# SuperCap.net
KiCad netlist of a schematic drawn in Altium Designer
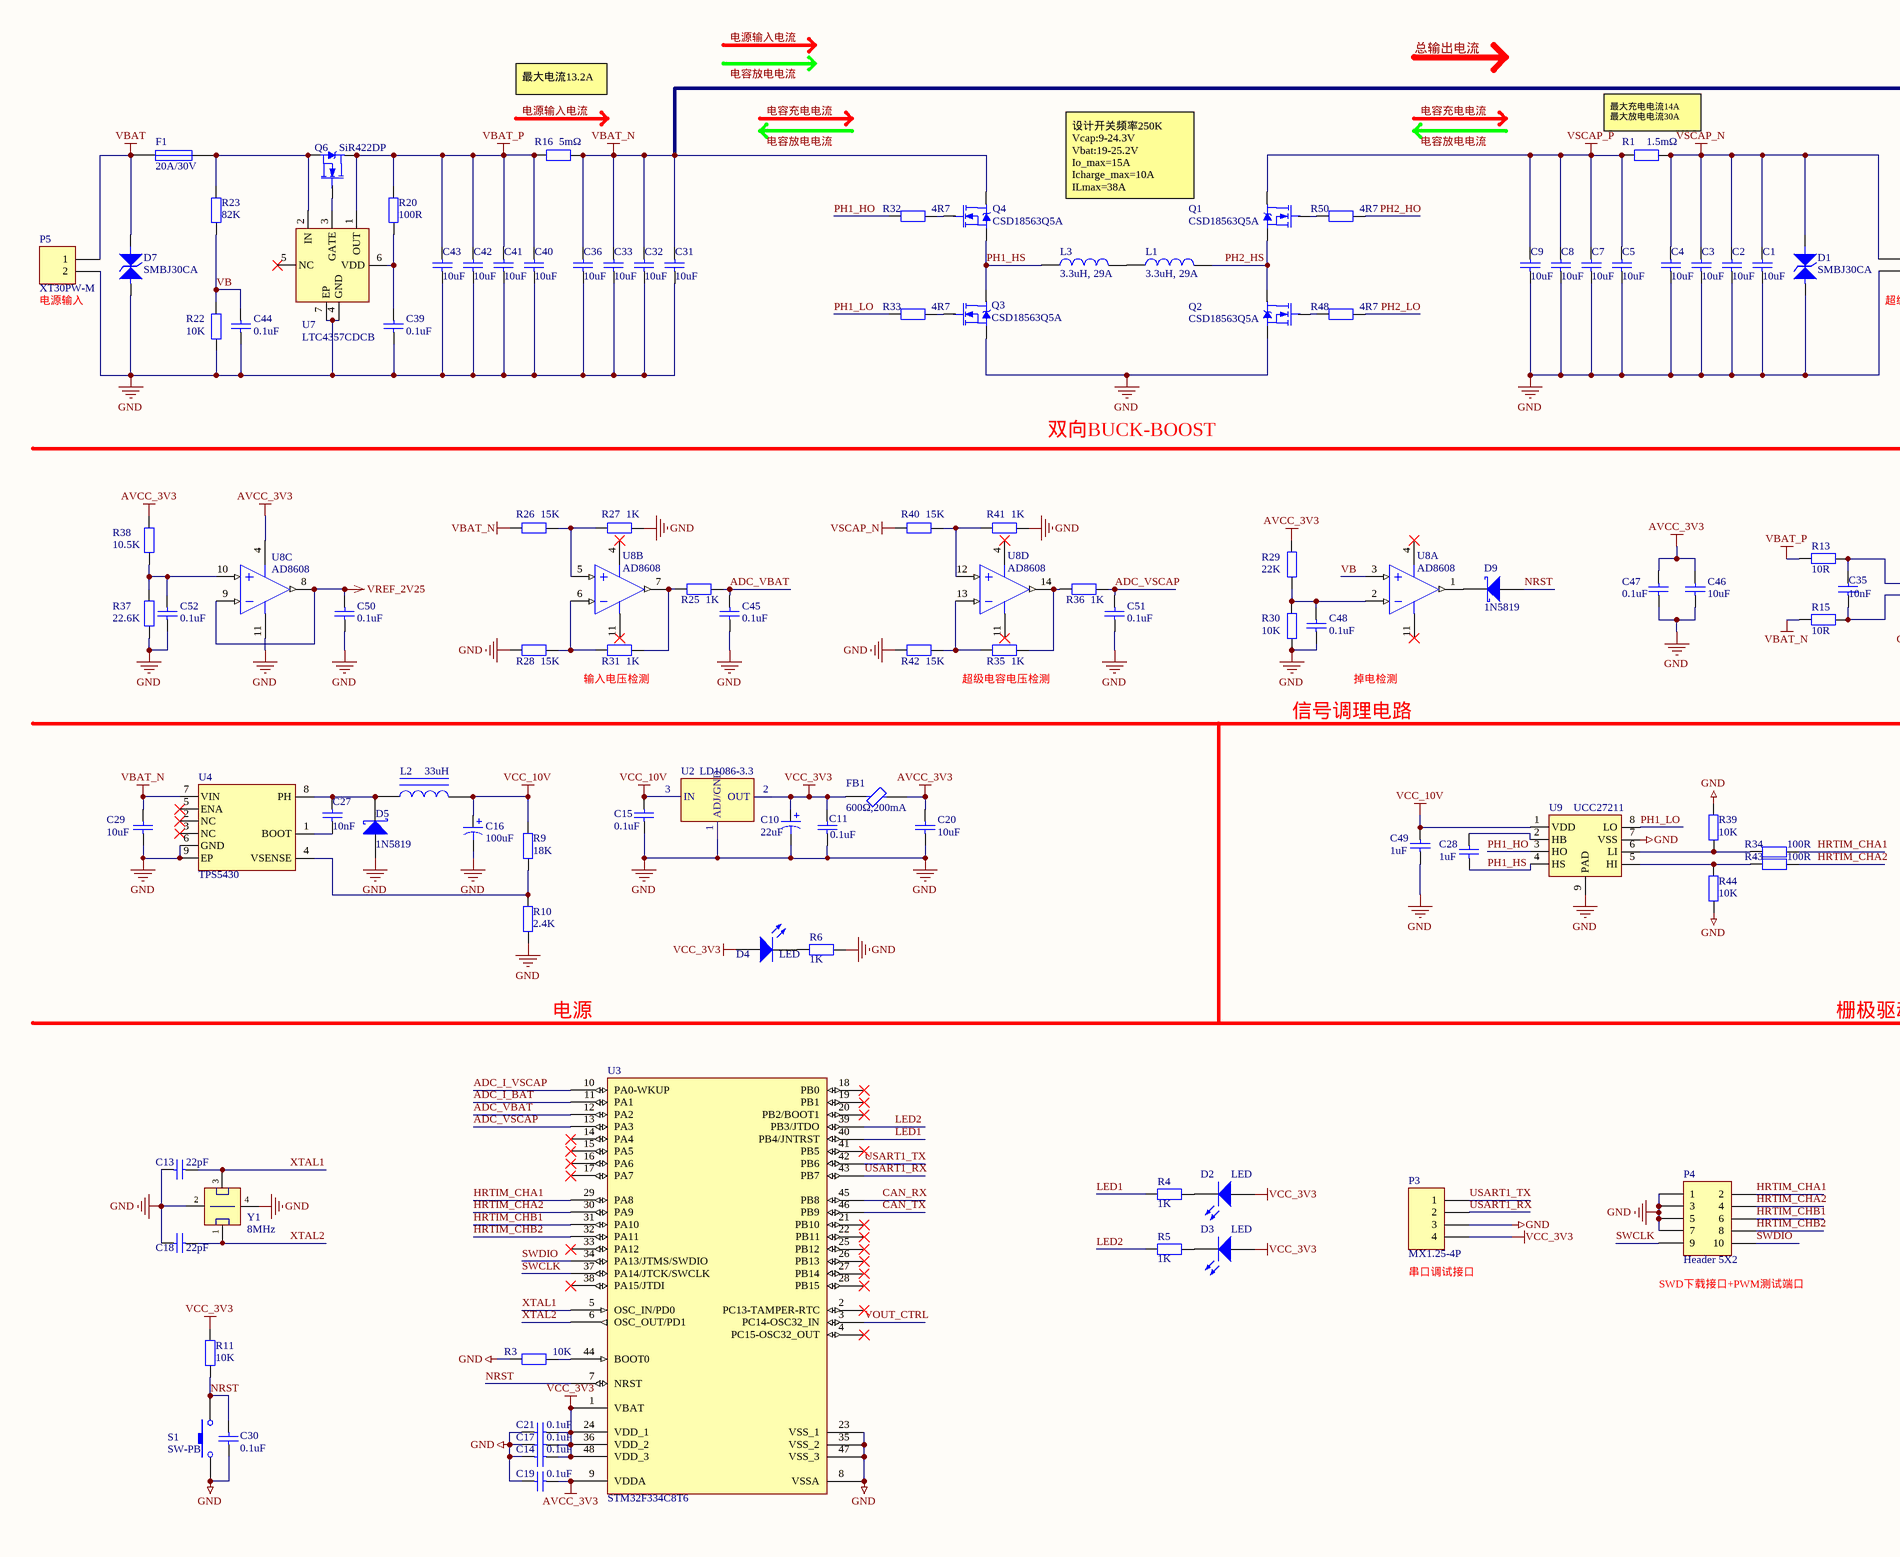
[diagram p0: SuperCap.SchDoc, left]
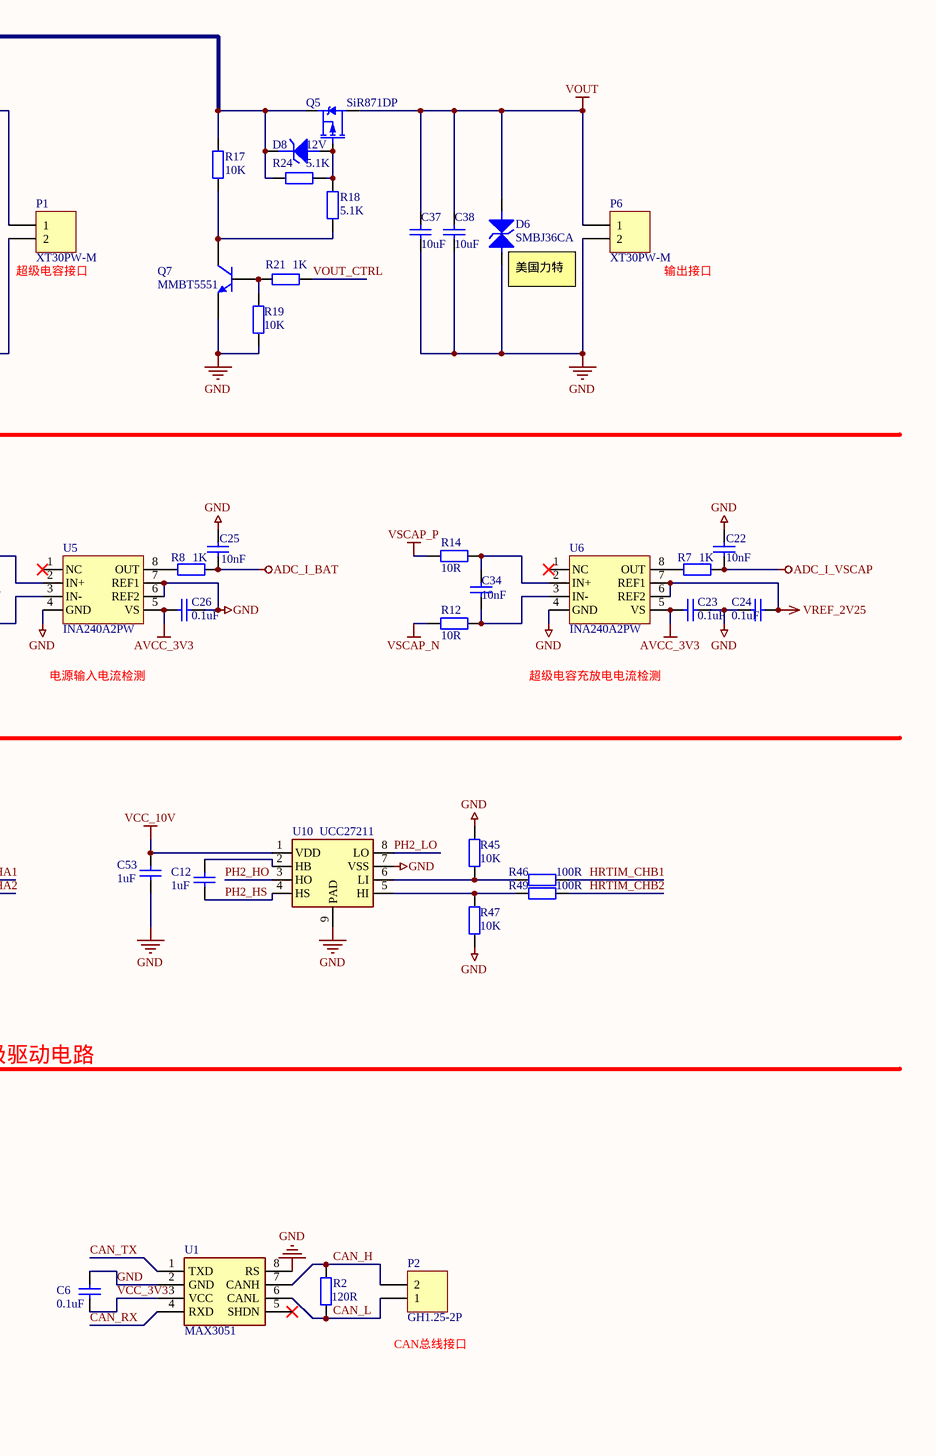
[diagram p1: SuperCap.SchDoc, right]

(export (version "E")
  (design (tool "Eeschema 10.0.6"))
  (components
    (comp (ref "C1")
      (value "10uF")
      (footprint "C 0805_M")
      (description "Capacitor")
      (libsource (lib "Miscellaneous Devices") (part "Cap"))
    )
    (comp (ref "C2")
      (value "10uF")
      (footprint "C 0805_M")
      (description "Capacitor")
      (libsource (lib "Miscellaneous Devices") (part "Cap"))
    )
    (comp (ref "C3")
      (value "10uF")
      (footprint "C 0805_M")
      (description "Capacitor")
      (libsource (lib "Miscellaneous Devices") (part "Cap"))
    )
    (comp (ref "C4")
      (value "10uF")
      (footprint "C 0805_M")
      (description "Capacitor")
      (libsource (lib "Miscellaneous Devices") (part "Cap"))
    )
    (comp (ref "C5")
      (value "10uF")
      (footprint "C 0805_M")
      (description "Capacitor")
      (libsource (lib "Miscellaneous Devices") (part "Cap"))
    )
    (comp (ref "C6")
      (value "0.1uF")
      (footprint "C 0603_M")
      (description "Capacitor")
      (libsource (lib "Miscellaneous Devices") (part "Cap"))
    )
    (comp (ref "C7")
      (value "10uF")
      (footprint "C 0805_M")
      (description "Capacitor")
      (libsource (lib "Miscellaneous Devices") (part "Cap"))
    )
    (comp (ref "C8")
      (value "10uF")
      (footprint "C 0805_M")
      (description "Capacitor")
      (libsource (lib "Miscellaneous Devices") (part "Cap"))
    )
    (comp (ref "C9")
      (value "10uF")
      (footprint "C 0805_M")
      (description "Capacitor")
      (libsource (lib "Miscellaneous Devices") (part "Cap"))
    )
    (comp (ref "C10")
      (value "22uF")
      (footprint "CD B(3528)")
      (description "Polarized Capacitor (Radial)")
      (libsource (lib "Miscellaneous Devices") (part "Cap Pol1"))
    )
    (comp (ref "C11")
      (value "0.1uF")
      (footprint "C 0603_M")
      (description "Capacitor")
      (libsource (lib "Miscellaneous Devices") (part "Cap"))
    )
    (comp (ref "C12")
      (value "1uF")
      (footprint "C 0603_M")
      (description "Capacitor")
      (libsource (lib "Miscellaneous Devices") (part "Cap"))
    )
    (comp (ref "C13")
      (value "22pF")
      (footprint "C 0603_M")
      (description "Capacitor")
      (fields (field (name "PUBLISHER") "Altium Limited"))
      (libsource (lib "Miscellaneous Devices") (part "Cap"))
    )
    (comp (ref "C14")
      (value "0.1uF")
      (footprint "C 0603_M")
      (description "Capacitor")
      (libsource (lib "Miscellaneous Devices") (part "Cap"))
    )
    (comp (ref "C15")
      (value "0.1uF")
      (footprint "C 0603_M")
      (description "Capacitor")
      (libsource (lib "Miscellaneous Devices") (part "Cap"))
    )
    (comp (ref "C16")
      (value "100uF")
      (footprint "CD C(6032)")
      (description "Polarized Capacitor (Radial)")
      (libsource (lib "Miscellaneous Devices") (part "Cap Pol1"))
    )
    (comp (ref "C17")
      (value "0.1uF")
      (footprint "C 0603_M")
      (description "Capacitor")
      (libsource (lib "Miscellaneous Devices") (part "Cap"))
    )
    (comp (ref "C18")
      (value "22pF")
      (footprint "C 0603_M")
      (description "Capacitor")
      (fields (field (name "PUBLISHER") "Altium Limited"))
      (libsource (lib "Miscellaneous Devices") (part "Cap"))
    )
    (comp (ref "C19")
      (value "0.1uF")
      (footprint "C 0603_M")
      (description "Capacitor")
      (libsource (lib "Miscellaneous Devices") (part "Cap"))
    )
    (comp (ref "C20")
      (value "10uF")
      (footprint "C 0603_M")
      (description "Capacitor")
      (libsource (lib "Miscellaneous Devices") (part "Cap"))
    )
    (comp (ref "C21")
      (value "0.1uF")
      (footprint "C 0603_M")
      (description "Capacitor")
      (libsource (lib "Miscellaneous Devices") (part "Cap"))
    )
    (comp (ref "C22")
      (value "10nF")
      (footprint "C 0603_M")
      (description "Capacitor")
      (fields (field (name "PUBLISHER") "Altium Limited"))
      (libsource (lib "Miscellaneous Devices") (part "Cap"))
    )
    (comp (ref "C23")
      (value "0.1uF")
      (footprint "C 0603_M")
      (description "Capacitor")
      (fields (field (name "PUBLISHER") "Altium Limited"))
      (libsource (lib "Miscellaneous Devices") (part "Cap"))
    )
    (comp (ref "C24")
      (value "0.1uF")
      (footprint "C 0603_M")
      (description "Capacitor")
      (fields (field (name "PUBLISHER") "Altium Limited"))
      (libsource (lib "Miscellaneous Devices") (part "Cap"))
    )
    (comp (ref "C25")
      (value "10nF")
      (footprint "C 0603_M")
      (description "Capacitor")
      (fields (field (name "PUBLISHER") "Altium Limited"))
      (libsource (lib "Miscellaneous Devices") (part "Cap"))
    )
    (comp (ref "C26")
      (value "0.1uF")
      (footprint "C 0603_M")
      (description "Capacitor")
      (fields (field (name "PUBLISHER") "Altium Limited"))
      (libsource (lib "Miscellaneous Devices") (part "Cap"))
    )
    (comp (ref "C27")
      (value "10nF")
      (footprint "C 0603_M")
      (description "Capacitor")
      (libsource (lib "Miscellaneous Devices") (part "Cap"))
    )
    (comp (ref "C28")
      (value "1uF")
      (footprint "C 0603_M")
      (description "Capacitor")
      (libsource (lib "Miscellaneous Devices") (part "Cap"))
    )
    (comp (ref "C29")
      (value "10uF")
      (footprint "C 0805_M")
      (description "Capacitor")
      (libsource (lib "Miscellaneous Devices") (part "Cap"))
    )
    (comp (ref "C30")
      (value "0.1uF")
      (footprint "C 0603_M")
      (description "Capacitor")
      (libsource (lib "Miscellaneous Devices") (part "Cap"))
    )
    (comp (ref "C31")
      (value "10uF")
      (footprint "C 0805_M")
      (description "Capacitor")
      (libsource (lib "Miscellaneous Devices") (part "Cap"))
    )
    (comp (ref "C32")
      (value "10uF")
      (footprint "C 0805_M")
      (description "Capacitor")
      (libsource (lib "Miscellaneous Devices") (part "Cap"))
    )
    (comp (ref "C33")
      (value "10uF")
      (footprint "C 0805_M")
      (description "Capacitor")
      (libsource (lib "Miscellaneous Devices") (part "Cap"))
    )
    (comp (ref "C34")
      (value "10nF")
      (footprint "C 0603_M")
      (description "Capacitor")
      (fields (field (name "PUBLISHER") "Altium Limited"))
      (libsource (lib "Miscellaneous Devices") (part "Cap"))
    )
    (comp (ref "C35")
      (value "10nF")
      (footprint "C 0603_M")
      (description "Capacitor")
      (fields (field (name "PUBLISHER") "Altium Limited"))
      (libsource (lib "Miscellaneous Devices") (part "Cap"))
    )
    (comp (ref "C36")
      (value "10uF")
      (footprint "C 0805_M")
      (description "Capacitor")
      (libsource (lib "Miscellaneous Devices") (part "Cap"))
    )
    (comp (ref "C37")
      (value "10uF")
      (footprint "C 0805_M")
      (description "Capacitor")
      (libsource (lib "Miscellaneous Devices") (part "Cap"))
    )
    (comp (ref "C38")
      (value "10uF")
      (footprint "C 0805_M")
      (description "Capacitor")
      (libsource (lib "Miscellaneous Devices") (part "Cap"))
    )
    (comp (ref "C39")
      (value "0.1uF")
      (footprint "C 0603_M")
      (description "Capacitor")
      (libsource (lib "Miscellaneous Devices") (part "Cap"))
    )
    (comp (ref "C40")
      (value "10uF")
      (footprint "C 0805_M")
      (description "Capacitor")
      (libsource (lib "Miscellaneous Devices") (part "Cap"))
    )
    (comp (ref "C41")
      (value "10uF")
      (footprint "C 0805_M")
      (description "Capacitor")
      (libsource (lib "Miscellaneous Devices") (part "Cap"))
    )
    (comp (ref "C42")
      (value "10uF")
      (footprint "C 0805_M")
      (description "Capacitor")
      (libsource (lib "Miscellaneous Devices") (part "Cap"))
    )
    (comp (ref "C43")
      (value "10uF")
      (footprint "C 0805_M")
      (description "Capacitor")
      (libsource (lib "Miscellaneous Devices") (part "Cap"))
    )
    (comp (ref "C44")
      (value "0.1uF")
      (footprint "C 0603_M")
      (description "Capacitor")
      (libsource (lib "Miscellaneous Devices") (part "Cap"))
    )
    (comp (ref "C45")
      (value "0.1uF")
      (footprint "C 0603_M")
      (description "Capacitor")
      (libsource (lib "Miscellaneous Devices") (part "Cap"))
    )
    (comp (ref "C46")
      (value "10uF")
      (footprint "C 0603_M")
      (description "Capacitor")
      (libsource (lib "Miscellaneous Devices") (part "Cap"))
    )
    (comp (ref "C47")
      (value "0.1uF")
      (footprint "C 0603_M")
      (description "Capacitor")
      (libsource (lib "Miscellaneous Devices") (part "Cap"))
    )
    (comp (ref "C48")
      (value "0.1uF")
      (footprint "C 0603_M")
      (description "Capacitor")
      (libsource (lib "Miscellaneous Devices") (part "Cap"))
    )
    (comp (ref "C49")
      (value "1uF")
      (footprint "C 0603_M")
      (description "Capacitor")
      (libsource (lib "Miscellaneous Devices") (part "Cap"))
    )
    (comp (ref "C50")
      (value "0.1uF")
      (footprint "C 0603_M")
      (description "Capacitor")
      (libsource (lib "Miscellaneous Devices") (part "Cap"))
    )
    (comp (ref "C51")
      (value "0.1uF")
      (footprint "C 0603_M")
      (description "Capacitor")
      (libsource (lib "Miscellaneous Devices") (part "Cap"))
    )
    (comp (ref "C52")
      (value "0.1uF")
      (footprint "C 0603_M")
      (description "Capacitor")
      (libsource (lib "Miscellaneous Devices") (part "Cap"))
    )
    (comp (ref "C53")
      (value "1uF")
      (footprint "C 0603_M")
      (description "Capacitor")
      (libsource (lib "Miscellaneous Devices") (part "Cap"))
    )
    (comp (ref "D1")
      (value "SMBJ30CA")
      (footprint "二极管-整流桥:SMB")
      (description "双向瞬态抑制二极管")
      (libsource (lib "二极管") (part "TVS"))
    )
    (comp (ref "D2")
      (value "LED")
      (footprint "LED 0603R")
      (description "Typical INFRARED GaAs LED")
      (libsource (lib "Miscellaneous Devices") (part "LED0"))
    )
    (comp (ref "D3")
      (value "LED")
      (footprint "LED 0603R")
      (description "Typical INFRARED GaAs LED")
      (libsource (lib "Miscellaneous Devices") (part "LED0"))
    )
    (comp (ref "D4")
      (value "LED")
      (footprint "LED 0603R")
      (description "Typical INFRARED GaAs LED")
      (libsource (lib "Miscellaneous Devices") (part "LED0"))
    )
    (comp (ref "D5")
      (value "1N5819")
      (footprint "SMA")
      (description "Schottky Rectifier")
      (libsource (lib "Miscellaneous Devices") (part "Diode 11DQ03"))
    )
    (comp (ref "D6")
      (value "SMBJ36CA")
      (footprint "二极管-整流桥:SMB")
      (description "双向瞬态抑制二极管")
      (libsource (lib "二极管") (part "TVS"))
    )
    (comp (ref "D7")
      (value "SMBJ30CA")
      (footprint "二极管-整流桥:SMB")
      (description "双向瞬态抑制二极管")
      (libsource (lib "二极管") (part "TVS"))
    )
    (comp (ref "D8")
      (value "12V")
      (footprint "SOD-123")
      (description "稳压二极管")
      (libsource (lib "二极管") (part "DIODE ZENER"))
    )
    (comp (ref "D9")
      (value "1N5819")
      (footprint "SOD-323")
      (description "Schottky Diode")
      (fields (field (name "PUBLISHER") "Altium Limited"))
      (libsource (lib "Miscellaneous Devices") (part "D Schottky"))
    )
    (comp (ref "F1")
      (value "20A/30V")
      (footprint "FU 1206")
      (description "Fuse")
      (fields (field (name "PUBLISHER") "Altium Limited"))
      (libsource (lib "Miscellaneous Devices") (part "Fuse 1"))
    )
    (comp (ref "FB1")
      (value "600Ω,200mA")
      (footprint "FB0603_M")
      (libsource (lib "my_library") (part "Ferrite Bead"))
    )
    (comp (ref "L1")
      (value "3.3uH, 29A")
      (footprint "WE-HCI_2212")
      (description "WE-HCI SMT Flat Wire High Current Inductor, size 2212, 3.3uH, 29A")
      (fields
        (field (name "MANUFACTURER PART NUMBER") "74435580330")
        (field (name "MANUFACTURER") "Wurth Elektronik")
      )
      (libsource (lib "WE-HCI (rev20b)") (part "74435580330"))
    )
    (comp (ref "L2")
      (value "33uH")
      (footprint "L-SMD-0630")
      (description "Magnetic-Core Inductor")
      (libsource (lib "Miscellaneous Devices") (part "Inductor Iron"))
    )
    (comp (ref "L3")
      (value "3.3uH, 29A")
      (footprint "WE-HCI_2212")
      (description "WE-HCI SMT Flat Wire High Current Inductor, size 2212, 3.3uH, 29A")
      (fields
        (field (name "MANUFACTURER PART NUMBER") "74435580330")
        (field (name "MANUFACTURER") "Wurth Elektronik")
      )
      (libsource (lib "WE-HCI (rev20b)") (part "74435580330"))
    )
    (comp (ref "P1")
      (value "XT30PW-M")
      (footprint "XT30PW-M")
      (description "Header, 2-Pin")
      (fields (field (name "PUBLISHER") "Altium Limited"))
      (libsource (lib "") (part "Header 2_1"))
    )
    (comp (ref "P2")
      (value "GH1.25-2P")
      (footprint "A1257WR-S-2P")
      (description "Header, 2-Pin")
      (fields (field (name "PUBLISHER") "Altium Limited"))
      (libsource (lib "Miscellaneous Connectors") (part "Header 2"))
    )
    (comp (ref "P3")
      (value "MX1.25-4P")
      (footprint "MX 1.25-WS-4P")
      (description "Header, 4-Pin")
      (fields (field (name "PUBLISHER") "Altium Limited"))
      (libsource (lib "Miscellaneous Connectors") (part "Header 4"))
    )
    (comp (ref "P4")
      (value "Header 5X2")
      (footprint "HDR2.54-LI-2x5P")
      (description "Header, 5-Pin, Dual row")
      (fields (field (name "PUBLISHER") "Altium Limited"))
      (libsource (lib "Miscellaneous Connectors") (part "Header 5X2"))
    )
    (comp (ref "P5")
      (value "XT30PW-M")
      (footprint "XT30PW-M")
      (description "Header, 2-Pin")
      (fields (field (name "PUBLISHER") "Altium Limited"))
      (libsource (lib "") (part "Header 2_2"))
    )
    (comp (ref "P6")
      (value "XT30PW-M")
      (footprint "XT30PW-M")
      (description "Header, 2-Pin")
      (fields (field (name "PUBLISHER") "Altium Limited"))
      (libsource (lib "") (part "Header 2_1"))
    )
    (comp (ref "Q1")
      (value "CSD18563Q5A")
      (footprint "PG-TDSON-8")
      (description "N沟道场效应管")
      (libsource (lib "MOS管") (part "N-MOS"))
    )
    (comp (ref "Q2")
      (value "CSD18563Q5A")
      (footprint "PG-TDSON-8")
      (description "N沟道场效应管")
      (libsource (lib "MOS管") (part "N-MOS"))
    )
    (comp (ref "Q3")
      (value "CSD18563Q5A")
      (footprint "PG-TDSON-8")
      (description "N沟道场效应管")
      (libsource (lib "MOS管") (part "N-MOS"))
    )
    (comp (ref "Q4")
      (value "CSD18563Q5A")
      (footprint "PG-TDSON-8")
      (description "N沟道场效应管")
      (libsource (lib "MOS管") (part "N-MOS"))
    )
    (comp (ref "Q5")
      (value "SiR871DP")
      (footprint "PG-TDSON-8")
      (description "P沟道场效应管")
      (libsource (lib "MOS管") (part "P-MOS"))
    )
    (comp (ref "Q6")
      (value "SiR422DP")
      (footprint "PG-TDSON-8")
      (description "N沟道场效应管")
      (libsource (lib "MOS管") (part "N-MOS"))
    )
    (comp (ref "Q7")
      (value "MMBT5551")
      (footprint "SOT23-3N")
      (description "NPN Bipolar Transistor")
      (fields (field (name "PUBLISHER") "Altium Limited"))
      (libsource (lib "Miscellaneous Devices") (part "NPN"))
    )
    (comp (ref "R1")
      (value "1.5mΩ")
      (footprint "R 2512_M")
      (description "Resistor")
      (fields (field (name "PUBLISHER") "Altium Limited"))
      (libsource (lib "") (part "Res2_1"))
    )
    (comp (ref "R2")
      (value "120R")
      (footprint "R 0603_M")
      (description "Resistor")
      (libsource (lib "") (part "Res2_1"))
    )
    (comp (ref "R3")
      (value "10K")
      (footprint "R 0603_M")
      (description "Resistor")
      (libsource (lib "") (part "Res2_2"))
    )
    (comp (ref "R4")
      (value "1K")
      (footprint "R 0603_M")
      (description "Resistor")
      (libsource (lib "") (part "Res2_2"))
    )
    (comp (ref "R5")
      (value "1K")
      (footprint "R 0603_M")
      (description "Resistor")
      (libsource (lib "") (part "Res2_2"))
    )
    (comp (ref "R6")
      (value "1K")
      (footprint "R 0603_M")
      (description "Resistor")
      (libsource (lib "Miscellaneous Devices") (part "Res2"))
    )
    (comp (ref "R7")
      (value "1K")
      (footprint "R 0603_M")
      (description "Resistor")
      (fields (field (name "PUBLISHER") "Altium Limited"))
      (libsource (lib "") (part "Res2_2"))
    )
    (comp (ref "R8")
      (value "1K")
      (footprint "R 0603_M")
      (description "Resistor")
      (fields (field (name "PUBLISHER") "Altium Limited"))
      (libsource (lib "") (part "Res2_2"))
    )
    (comp (ref "R9")
      (value "18K")
      (footprint "R 0603_M")
      (description "Resistor")
      (libsource (lib "") (part "Res2_1"))
    )
    (comp (ref "R10")
      (value "2.4K")
      (footprint "R 0603_M")
      (description "Resistor")
      (libsource (lib "") (part "Res2_1"))
    )
    (comp (ref "R11")
      (value "10K")
      (footprint "R 0603_M")
      (description "Resistor")
      (libsource (lib "") (part "Res2_3"))
    )
    (comp (ref "R12")
      (value "10R")
      (footprint "R 0603_M")
      (description "Resistor")
      (fields (field (name "PUBLISHER") "Altium Limited"))
      (libsource (lib "") (part "Res2_1"))
    )
    (comp (ref "R13")
      (value "10R")
      (footprint "R 0603_M")
      (description "Resistor")
      (fields (field (name "PUBLISHER") "Altium Limited"))
      (libsource (lib "") (part "Res2_1"))
    )
    (comp (ref "R14")
      (value "10R")
      (footprint "R 0603_M")
      (description "Resistor")
      (fields (field (name "PUBLISHER") "Altium Limited"))
      (libsource (lib "") (part "Res2_1"))
    )
    (comp (ref "R15")
      (value "10R")
      (footprint "R 0603_M")
      (description "Resistor")
      (fields (field (name "PUBLISHER") "Altium Limited"))
      (libsource (lib "") (part "Res2_1"))
    )
    (comp (ref "R16")
      (value "5mΩ")
      (footprint "R 2512_M")
      (description "Resistor")
      (fields (field (name "PUBLISHER") "Altium Limited"))
      (libsource (lib "") (part "Res2_3"))
    )
    (comp (ref "R17")
      (value "10K")
      (footprint "R 0603_M")
      (description "Resistor")
      (libsource (lib "") (part "Res2_3"))
    )
    (comp (ref "R18")
      (value "5.1K")
      (footprint "R 0603_M")
      (description "Resistor")
      (libsource (lib "") (part "Res2_3"))
    )
    (comp (ref "R19")
      (value "10K")
      (footprint "R 0603_M")
      (description "Resistor")
      (libsource (lib "") (part "Res2_1"))
    )
    (comp (ref "R20")
      (value "100R")
      (footprint "R 0603_M")
      (description "Resistor")
      (libsource (lib "") (part "Res2_3"))
    )
    (comp (ref "R21")
      (value "1K")
      (footprint "R 0603_M")
      (description "Resistor")
      (libsource (lib "Miscellaneous Devices") (part "Res2"))
    )
    (comp (ref "R22")
      (value "10K")
      (footprint "R 0603_M")
      (description "Resistor")
      (libsource (lib "") (part "Res2_3"))
    )
    (comp (ref "R23")
      (value "82K")
      (footprint "R 0603_M")
      (description "Resistor")
      (libsource (lib "") (part "Res2_3"))
    )
    (comp (ref "R24")
      (value "5.1K")
      (footprint "R 0603_M")
      (description "Resistor")
      (libsource (lib "Miscellaneous Devices") (part "Res2"))
    )
    (comp (ref "R25")
      (value "1K")
      (footprint "R 0603_M")
      (description "Resistor")
      (libsource (lib "") (part "Res2_2"))
    )
    (comp (ref "R26")
      (value "15K")
      (footprint "R 0603_M")
      (description "Resistor")
      (libsource (lib "") (part "Res2_2"))
    )
    (comp (ref "R27")
      (value "1K")
      (footprint "R 0603_M")
      (description "Resistor")
      (libsource (lib "Miscellaneous Devices") (part "Res2"))
    )
    (comp (ref "R28")
      (value "15K")
      (footprint "R 0603_M")
      (description "Resistor")
      (libsource (lib "") (part "Res2_2"))
    )
    (comp (ref "R29")
      (value "22K")
      (footprint "R 0603_M")
      (description "Resistor")
      (libsource (lib "") (part "Res2_1"))
    )
    (comp (ref "R30")
      (value "10K")
      (footprint "R 0603_M")
      (description "Resistor")
      (libsource (lib "") (part "Res2_1"))
    )
    (comp (ref "R31")
      (value "1K")
      (footprint "R 0603_M")
      (description "Resistor")
      (libsource (lib "") (part "Res2_2"))
    )
    (comp (ref "R32")
      (value "4R7")
      (footprint "R 0805_M")
      (description "Resistor")
      (libsource (lib "") (part "Res2_2"))
    )
    (comp (ref "R33")
      (value "4R7")
      (footprint "R 0805_M")
      (description "Resistor")
      (libsource (lib "") (part "Res2_2"))
    )
    (comp (ref "R34")
      (value "100R")
      (footprint "R 0603_M")
      (description "Resistor")
      (libsource (lib "") (part "Res2_2"))
    )
    (comp (ref "R35")
      (value "1K")
      (footprint "R 0603_M")
      (description "Resistor")
      (libsource (lib "") (part "Res2_2"))
    )
    (comp (ref "R36")
      (value "1K")
      (footprint "R 0603_M")
      (description "Resistor")
      (libsource (lib "") (part "Res2_2"))
    )
    (comp (ref "R37")
      (value "22.6K")
      (footprint "R 0603_M")
      (description "Resistor")
      (libsource (lib "") (part "Res2_1"))
    )
    (comp (ref "R38")
      (value "10.5K")
      (footprint "R 0603_M")
      (description "Resistor")
      (libsource (lib "") (part "Res2_1"))
    )
    (comp (ref "R39")
      (value "10K")
      (footprint "R 0603_M")
      (description "Resistor")
      (libsource (lib "") (part "Res2_1"))
    )
    (comp (ref "R40")
      (value "15K")
      (footprint "R 0603_M")
      (description "Resistor")
      (libsource (lib "") (part "Res2_2"))
    )
    (comp (ref "R41")
      (value "1K")
      (footprint "R 0603_M")
      (description "Resistor")
      (libsource (lib "Miscellaneous Devices") (part "Res2"))
    )
    (comp (ref "R42")
      (value "15K")
      (footprint "R 0603_M")
      (description "Resistor")
      (libsource (lib "") (part "Res2_2"))
    )
    (comp (ref "R43")
      (value "100R")
      (footprint "R 0603_M")
      (description "Resistor")
      (libsource (lib "") (part "Res2_2"))
    )
    (comp (ref "R44")
      (value "10K")
      (footprint "R 0603_M")
      (description "Resistor")
      (libsource (lib "") (part "Res2_1"))
    )
    (comp (ref "R45")
      (value "10K")
      (footprint "R 0603_M")
      (description "Resistor")
      (libsource (lib "") (part "Res2_1"))
    )
    (comp (ref "R46")
      (value "100R")
      (footprint "R 0603_M")
      (description "Resistor")
      (libsource (lib "") (part "Res2_2"))
    )
    (comp (ref "R47")
      (value "10K")
      (footprint "R 0603_M")
      (description "Resistor")
      (libsource (lib "") (part "Res2_1"))
    )
    (comp (ref "R48")
      (value "4R7")
      (footprint "R 0805_M")
      (description "Resistor")
      (libsource (lib "") (part "Res2_2"))
    )
    (comp (ref "R49")
      (value "100R")
      (footprint "R 0603_M")
      (description "Resistor")
      (libsource (lib "") (part "Res2_2"))
    )
    (comp (ref "R50")
      (value "4R7")
      (footprint "R 0805_M")
      (description "Resistor")
      (libsource (lib "") (part "Res2_2"))
    )
    (comp (ref "S1")
      (value "SW-PB")
      (footprint "TS-1101")
      (description "Switch")
      (fields (field (name "PUBLISHER") "Altium Limited"))
      (libsource (lib "Miscellaneous Devices") (part "SW-PB"))
    )
    (comp (ref "U1") (value "MAX3051") (footprint "SOT23-8N") (libsource (lib "my_library") (part "MAX3051")))
    (comp (ref "U2") (value "LD1086-3.3") (footprint "TO252") (libsource (lib "my_library") (part "AMS1086")))
    (comp (ref "U3")
      (value "STM32F334C8T6")
      (footprint "LQFP48 7X7_N")
      (libsource (lib "STM32系列") (part "STM32F103C8T6"))
    )
    (comp (ref "U4")
      (value "TPS5430")
      (footprint "SOIC-8-EP")
      (libsource (lib "my_library") (part "TPS5430"))
    )
    (comp (ref "U5")
      (value "INA240A2PW")
      (footprint "SSOP8")
      (libsource (lib "my_library") (part "INA240 PW"))
    )
    (comp (ref "U6")
      (value "INA240A2PW")
      (footprint "SSOP8")
      (libsource (lib "my_library") (part "INA240 PW"))
    )
    (comp (ref "U7")
      (value "LTC4357CDCB")
      (footprint "DFN-6_2x3_0.5")
      (libsource (lib "my_library") (part "LTC4357CDCB"))
    )
    (comp (ref "U8")
      (value "AD8608")
      (footprint "SOP14_N")
      (fields (field (name "MANUFACTURER") "Analog Devices") (field (name "PARTNUMBER") "AD8608ARZ-REEL7"))
      (libsource (lib "Analog Devices Operational Amplifiers") (part "AD8608ARZ-REEL7"))
    )
    (comp (ref "U9")
      (value "UCC27211")
      (footprint "SOIC-8-EP")
      (libsource (lib "my_library") (part "UCC27211"))
    )
    (comp (ref "U10")
      (value "UCC27211")
      (footprint "SOIC-8-EP")
      (libsource (lib "my_library") (part "UCC27211"))
    )
    (comp (ref "Y1") (value "8MHz") (footprint "OSC-3225-4P") (libsource (lib "my_library") (part "XTAL")))
  )
  (nets
    (net (code "1") (name "/ADC_VBAT") (class "Default")
      (node (ref "C45") (pin "2") (pinfunction "2_2") (pintype "passive"))
      (node (ref "R25") (pin "2") (pinfunction "2_2") (pintype "passive"))
      (node (ref "U3") (pin "12") (pinfunction "PA2_12") (pintype "bidirectional"))
    )
    (net (code "2") (name "/ADC_VSCAP") (class "Default")
      (node (ref "C51") (pin "2") (pinfunction "2_2") (pintype "passive"))
      (node (ref "R36") (pin "2") (pinfunction "2_2") (pintype "passive"))
      (node (ref "U3") (pin "13") (pinfunction "PA3_13") (pintype "bidirectional"))
    )
    (net (code "3") (name "/CAN_H") (class "Default")
      (node (ref "P2") (pin "2") (pinfunction "2_2") (pintype "passive"))
      (node (ref "R2") (pin "1") (pinfunction "1_1") (pintype "passive"))
      (node (ref "U1") (pin "7") (pinfunction "CANH_7") (pintype "passive"))
    )
    (net (code "4") (name "/CAN_L") (class "Default")
      (node (ref "P2") (pin "1") (pinfunction "1_1") (pintype "passive"))
      (node (ref "R2") (pin "2") (pinfunction "2_2") (pintype "passive"))
      (node (ref "U1") (pin "6") (pinfunction "CANL_6") (pintype "passive"))
    )
    (net (code "5") (name "/CAN_RX") (class "Default")
      (node (ref "U1") (pin "4") (pinfunction "RXD_4") (pintype "passive"))
      (node (ref "U3") (pin "45") (pinfunction "PB8_45") (pintype "bidirectional"))
    )
    (net (code "6") (name "/CAN_TX") (class "Default")
      (node (ref "U1") (pin "1") (pinfunction "TXD_1") (pintype "passive"))
      (node (ref "U3") (pin "46") (pinfunction "PB9_46") (pintype "bidirectional"))
    )
    (net (code "7") (name "/HRTIM_CHA1") (class "Default")
      (node (ref "P4") (pin "2") (pinfunction "2_2") (pintype "passive"))
      (node (ref "R34") (pin "2") (pinfunction "2_2") (pintype "passive"))
      (node (ref "U3") (pin "29") (pinfunction "PA8_29") (pintype "bidirectional"))
    )
    (net (code "8") (name "/HRTIM_CHA2") (class "Default")
      (node (ref "P4") (pin "4") (pinfunction "4_4") (pintype "passive"))
      (node (ref "R43") (pin "2") (pinfunction "2_2") (pintype "passive"))
      (node (ref "U3") (pin "30") (pinfunction "PA9_30") (pintype "bidirectional"))
    )
    (net (code "9") (name "/HRTIM_CHB1") (class "Default")
      (node (ref "P4") (pin "6") (pinfunction "6_6") (pintype "passive"))
      (node (ref "R46") (pin "2") (pinfunction "2_2") (pintype "passive"))
      (node (ref "U3") (pin "31") (pinfunction "PA10_31") (pintype "bidirectional"))
    )
    (net (code "10") (name "/HRTIM_CHB2") (class "Default")
      (node (ref "P4") (pin "8") (pinfunction "8_8") (pintype "passive"))
      (node (ref "R49") (pin "2") (pinfunction "2_2") (pintype "passive"))
      (node (ref "U3") (pin "32") (pinfunction "PA11_32") (pintype "bidirectional"))
    )
    (net (code "11") (name "/LED1") (class "Default")
      (node (ref "R4") (pin "1") (pinfunction "1_1") (pintype "passive"))
      (node (ref "U3") (pin "40") (pinfunction "PB4/JNTRST_40") (pintype "bidirectional"))
    )
    (net (code "12") (name "/LED2") (class "Default")
      (node (ref "R5") (pin "1") (pinfunction "1_1") (pintype "passive"))
      (node (ref "U3") (pin "39") (pinfunction "PB3/JTDO_39") (pintype "bidirectional"))
    )
    (net (code "13") (name "/NRST") (class "Default")
      (node (ref "C30") (pin "2") (pinfunction "2_2") (pintype "passive"))
      (node (ref "D9") (pin "1") (pinfunction "A_1") (pintype "passive"))
      (node (ref "R11") (pin "1") (pinfunction "1_1") (pintype "passive"))
      (node (ref "S1") (pin "2") (pinfunction "2_2") (pintype "passive"))
      (node (ref "U3") (pin "7") (pinfunction "NRST_7") (pintype "bidirectional"))
    )
    (net (code "14") (name "/PH1_HO") (class "Default")
      (node (ref "R32") (pin "1") (pinfunction "1_1") (pintype "passive"))
      (node (ref "U9") (pin "3") (pinfunction "HO_3") (pintype "passive"))
    )
    (net (code "15") (name "/PH1_HS") (class "Default")
      (node (ref "C28") (pin "1") (pinfunction "1_1") (pintype "passive"))
      (node (ref "L3") (pin "1") (pinfunction "1_1") (pintype "passive"))
      (node (ref "Q3") (pin "D") (pinfunction "D_D") (pintype "passive"))
      (node (ref "Q4") (pin "S") (pinfunction "S_S") (pintype "passive"))
      (node (ref "U9") (pin "4") (pinfunction "HS_4") (pintype "passive"))
    )
    (net (code "16") (name "/PH1_LO") (class "Default")
      (node (ref "R33") (pin "1") (pinfunction "1_1") (pintype "passive"))
      (node (ref "U9") (pin "8") (pinfunction "LO_8") (pintype "passive"))
    )
    (net (code "17") (name "/PH2_HO") (class "Default")
      (node (ref "R50") (pin "2") (pinfunction "2_2") (pintype "passive"))
      (node (ref "U10") (pin "3") (pinfunction "HO_3") (pintype "passive"))
    )
    (net (code "18") (name "/PH2_HS") (class "Default")
      (node (ref "C12") (pin "1") (pinfunction "1_1") (pintype "passive"))
      (node (ref "L1") (pin "2") (pinfunction "2_2") (pintype "passive"))
      (node (ref "Q1") (pin "S") (pinfunction "S_S") (pintype "passive"))
      (node (ref "Q2") (pin "D") (pinfunction "D_D") (pintype "passive"))
      (node (ref "U10") (pin "4") (pinfunction "HS_4") (pintype "passive"))
    )
    (net (code "19") (name "/PH2_LO") (class "Default")
      (node (ref "R48") (pin "2") (pinfunction "2_2") (pintype "passive"))
      (node (ref "U10") (pin "8") (pinfunction "LO_8") (pintype "passive"))
    )
    (net (code "20") (name "/SWCLK") (class "Default")
      (node (ref "P4") (pin "9") (pinfunction "9_9") (pintype "passive"))
      (node (ref "U3") (pin "37") (pinfunction "PA14/JTCK/SWCLK_37") (pintype "bidirectional"))
    )
    (net (code "21") (name "/SWDIO") (class "Default")
      (node (ref "P4") (pin "10") (pinfunction "10_10") (pintype "passive"))
      (node (ref "U3") (pin "34") (pinfunction "PA13/JTMS/SWDIO_34") (pintype "bidirectional"))
    )
    (net (code "22") (name "/USART1_RX") (class "Default")
      (node (ref "P3") (pin "2") (pinfunction "2_2") (pintype "passive"))
      (node (ref "U3") (pin "43") (pinfunction "PB7_43") (pintype "bidirectional"))
    )
    (net (code "23") (name "/USART1_TX") (class "Default")
      (node (ref "P3") (pin "1") (pinfunction "1_1") (pintype "passive"))
      (node (ref "U3") (pin "42") (pinfunction "PB6_42") (pintype "bidirectional"))
    )
    (net (code "24") (name "/VB") (class "Default")
      (node (ref "C44") (pin "2") (pinfunction "2_2") (pintype "passive"))
      (node (ref "R22") (pin "2") (pinfunction "2_2") (pintype "passive"))
      (node (ref "R23") (pin "1") (pinfunction "1_1") (pintype "passive"))
      (node (ref "U8") (pin "3") (pinfunction "+IN_A_3") (pintype "input"))
    )
    (net (code "25") (name "/VOUT_CTRL") (class "Default")
      (node (ref "R21") (pin "1") (pinfunction "1_1") (pintype "passive"))
      (node (ref "U3") (pin "3") (pinfunction "PC14-OSC32_IN_3") (pintype "bidirectional"))
    )
    (net (code "26") (name "/XTAL1") (class "Default")
      (node (ref "C13") (pin "2") (pinfunction "2_2") (pintype "passive"))
      (node (ref "U3") (pin "5") (pinfunction "OSC_IN/PD0_5") (pintype "input"))
      (node (ref "Y1") (pin "3") (pinfunction "3_3") (pintype "passive"))
    )
    (net (code "27") (name "/XTAL2") (class "Default")
      (node (ref "C18") (pin "2") (pinfunction "2_2") (pintype "passive"))
      (node (ref "U3") (pin "6") (pinfunction "OSC_OUT/PD1_6") (pintype "output"))
      (node (ref "Y1") (pin "1") (pinfunction "1_1") (pintype "passive"))
    )
    (net (code "28") (name "ADC_I_BAT") (class "Default")
      (node (ref "C25") (pin "1") (pinfunction "1_1") (pintype "passive"))
      (node (ref "R8") (pin "2") (pinfunction "2_2") (pintype "passive"))
      (node (ref "U3") (pin "11") (pinfunction "PA1_11") (pintype "bidirectional"))
    )
    (net (code "29") (name "ADC_I_VSCAP") (class "Default")
      (node (ref "C22") (pin "1") (pinfunction "1_1") (pintype "passive"))
      (node (ref "R7") (pin "2") (pinfunction "2_2") (pintype "passive"))
      (node (ref "U3") (pin "10") (pinfunction "PA0-WKUP_10") (pintype "bidirectional"))
    )
    (net (code "30") (name "AVCC_3V3") (class "Default")
      (node (ref "C19") (pin "2") (pinfunction "2_2") (pintype "passive"))
      (node (ref "C20") (pin "2") (pinfunction "2_2") (pintype "passive"))
      (node (ref "C23") (pin "2") (pinfunction "2_2") (pintype "passive"))
      (node (ref "C26") (pin "2") (pinfunction "2_2") (pintype "passive"))
      (node (ref "C46") (pin "2") (pinfunction "2_2") (pintype "passive"))
      (node (ref "C47") (pin "2") (pinfunction "2_2") (pintype "passive"))
      (node (ref "FB1") (pin "2") (pinfunction "2_2") (pintype "passive"))
      (node (ref "R29") (pin "1") (pinfunction "1_1") (pintype "passive"))
      (node (ref "R38") (pin "1") (pinfunction "1_1") (pintype "passive"))
      (node (ref "U3") (pin "9") (pinfunction "VDDA_9") (pintype "power_in"))
      (node (ref "U5") (pin "5") (pinfunction "VS_5") (pintype "passive"))
      (node (ref "U6") (pin "5") (pinfunction "VS_5") (pintype "passive"))
      (node (ref "U8") (pin "4") (pinfunction "+V_4") (pintype "power_in"))
    )
    (net (code "31") (name "GND") (class "Default")
      (node (ref "C1") (pin "1") (pinfunction "1_1") (pintype "passive"))
      (node (ref "C10") (pin "2") (pinfunction "2_2") (pintype "passive"))
      (node (ref "C11") (pin "1") (pinfunction "1_1") (pintype "passive"))
      (node (ref "C13") (pin "1") (pinfunction "1_1") (pintype "passive"))
      (node (ref "C14") (pin "1") (pinfunction "1_1") (pintype "passive"))
      (node (ref "C15") (pin "2") (pinfunction "2_2") (pintype "passive"))
      (node (ref "C16") (pin "2") (pinfunction "2_2") (pintype "passive"))
      (node (ref "C17") (pin "1") (pinfunction "1_1") (pintype "passive"))
      (node (ref "C18") (pin "1") (pinfunction "1_1") (pintype "passive"))
      (node (ref "C19") (pin "1") (pinfunction "1_1") (pintype "passive"))
      (node (ref "C2") (pin "1") (pinfunction "1_1") (pintype "passive"))
      (node (ref "C20") (pin "1") (pinfunction "1_1") (pintype "passive"))
      (node (ref "C21") (pin "1") (pinfunction "1_1") (pintype "passive"))
      (node (ref "C22") (pin "2") (pinfunction "2_2") (pintype "passive"))
      (node (ref "C23") (pin "1") (pinfunction "1_1") (pintype "passive"))
      (node (ref "C24") (pin "2") (pinfunction "2_2") (pintype "passive"))
      (node (ref "C25") (pin "2") (pinfunction "2_2") (pintype "passive"))
      (node (ref "C26") (pin "1") (pinfunction "1_1") (pintype "passive"))
      (node (ref "C29") (pin "1") (pinfunction "1_1") (pintype "passive"))
      (node (ref "C3") (pin "1") (pinfunction "1_1") (pintype "passive"))
      (node (ref "C30") (pin "1") (pinfunction "1_1") (pintype "passive"))
      (node (ref "C31") (pin "1") (pinfunction "1_1") (pintype "passive"))
      (node (ref "C32") (pin "1") (pinfunction "1_1") (pintype "passive"))
      (node (ref "C33") (pin "1") (pinfunction "1_1") (pintype "passive"))
      (node (ref "C36") (pin "1") (pinfunction "1_1") (pintype "passive"))
      (node (ref "C37") (pin "1") (pinfunction "1_1") (pintype "passive"))
      (node (ref "C38") (pin "1") (pinfunction "1_1") (pintype "passive"))
      (node (ref "C39") (pin "1") (pinfunction "1_1") (pintype "passive"))
      (node (ref "C4") (pin "1") (pinfunction "1_1") (pintype "passive"))
      (node (ref "C40") (pin "1") (pinfunction "1_1") (pintype "passive"))
      (node (ref "C41") (pin "1") (pinfunction "1_1") (pintype "passive"))
      (node (ref "C42") (pin "1") (pinfunction "1_1") (pintype "passive"))
      (node (ref "C43") (pin "1") (pinfunction "1_1") (pintype "passive"))
      (node (ref "C44") (pin "1") (pinfunction "1_1") (pintype "passive"))
      (node (ref "C45") (pin "1") (pinfunction "1_1") (pintype "passive"))
      (node (ref "C46") (pin "1") (pinfunction "1_1") (pintype "passive"))
      (node (ref "C47") (pin "1") (pinfunction "1_1") (pintype "passive"))
      (node (ref "C48") (pin "1") (pinfunction "1_1") (pintype "passive"))
      (node (ref "C49") (pin "1") (pinfunction "1_1") (pintype "passive"))
      (node (ref "C5") (pin "1") (pinfunction "1_1") (pintype "passive"))
      (node (ref "C50") (pin "1") (pinfunction "1_1") (pintype "passive"))
      (node (ref "C51") (pin "1") (pinfunction "1_1") (pintype "passive"))
      (node (ref "C52") (pin "1") (pinfunction "1_1") (pintype "passive"))
      (node (ref "C53") (pin "1") (pinfunction "1_1") (pintype "passive"))
      (node (ref "C6") (pin "2") (pinfunction "2_2") (pintype "passive"))
      (node (ref "C7") (pin "1") (pinfunction "1_1") (pintype "passive"))
      (node (ref "C8") (pin "1") (pinfunction "1_1") (pintype "passive"))
      (node (ref "C9") (pin "1") (pinfunction "1_1") (pintype "passive"))
      (node (ref "D1") (pin "A") (pinfunction "A_A") (pintype "passive"))
      (node (ref "D5") (pin "1") (pinfunction "A_1") (pintype "passive"))
      (node (ref "D6") (pin "A") (pinfunction "A_A") (pintype "passive"))
      (node (ref "D7") (pin "A") (pinfunction "A_A") (pintype "passive"))
      (node (ref "P1") (pin "2") (pinfunction "2_2") (pintype "passive"))
      (node (ref "P3") (pin "3") (pinfunction "3_3") (pintype "passive"))
      (node (ref "P4") (pin "1") (pinfunction "1_1") (pintype "passive"))
      (node (ref "P4") (pin "3") (pinfunction "3_3") (pintype "passive"))
      (node (ref "P4") (pin "5") (pinfunction "5_5") (pintype "passive"))
      (node (ref "P4") (pin "7") (pinfunction "7_7") (pintype "passive"))
      (node (ref "P5") (pin "2") (pinfunction "2_2") (pintype "passive"))
      (node (ref "P6") (pin "2") (pinfunction "2_2") (pintype "passive"))
      (node (ref "Q2") (pin "S") (pinfunction "S_S") (pintype "passive"))
      (node (ref "Q3") (pin "S") (pinfunction "S_S") (pintype "passive"))
      (node (ref "Q7") (pin "3") (pinfunction "E_3") (pintype "passive"))
      (node (ref "R10") (pin "2") (pinfunction "2_2") (pintype "passive"))
      (node (ref "R19") (pin "2") (pinfunction "2_2") (pintype "passive"))
      (node (ref "R22") (pin "1") (pinfunction "1_1") (pintype "passive"))
      (node (ref "R27") (pin "1") (pinfunction "1_1") (pintype "passive"))
      (node (ref "R28") (pin "1") (pinfunction "1_1") (pintype "passive"))
      (node (ref "R3") (pin "1") (pinfunction "1_1") (pintype "passive"))
      (node (ref "R30") (pin "2") (pinfunction "2_2") (pintype "passive"))
      (node (ref "R37") (pin "2") (pinfunction "2_2") (pintype "passive"))
      (node (ref "R39") (pin "1") (pinfunction "1_1") (pintype "passive"))
      (node (ref "R41") (pin "1") (pinfunction "1_1") (pintype "passive"))
      (node (ref "R42") (pin "1") (pinfunction "1_1") (pintype "passive"))
      (node (ref "R44") (pin "2") (pinfunction "2_2") (pintype "passive"))
      (node (ref "R45") (pin "1") (pinfunction "1_1") (pintype "passive"))
      (node (ref "R47") (pin "2") (pinfunction "2_2") (pintype "passive"))
      (node (ref "R6") (pin "1") (pinfunction "1_1") (pintype "passive"))
      (node (ref "S1") (pin "1") (pinfunction "1_1") (pintype "passive"))
      (node (ref "U1") (pin "2") (pinfunction "GND_2") (pintype "passive"))
      (node (ref "U1") (pin "8") (pinfunction "RS_8") (pintype "passive"))
      (node (ref "U10") (pin "7") (pinfunction "VSS_7") (pintype "passive"))
      (node (ref "U10") (pin "9") (pinfunction "PAD_9") (pintype "passive"))
      (node (ref "U2") (pin "1") (pinfunction "ADJ/GND_1") (pintype "passive"))
      (node (ref "U3") (pin "23") (pinfunction "VSS_1_23") (pintype "power_in"))
      (node (ref "U3") (pin "35") (pinfunction "VSS_2_35") (pintype "power_in"))
      (node (ref "U3") (pin "47") (pinfunction "VSS_3_47") (pintype "power_in"))
      (node (ref "U3") (pin "8") (pinfunction "VSSA_8") (pintype "power_in"))
      (node (ref "U4") (pin "6") (pinfunction "GND_6") (pintype "passive"))
      (node (ref "U4") (pin "9") (pinfunction "EP_9") (pintype "passive"))
      (node (ref "U5") (pin "4") (pinfunction "GND_4") (pintype "passive"))
      (node (ref "U5") (pin "6") (pinfunction "REF2_6") (pintype "passive"))
      (node (ref "U5") (pin "7") (pinfunction "REF1_7") (pintype "passive"))
      (node (ref "U6") (pin "4") (pinfunction "GND_4") (pintype "passive"))
      (node (ref "U7") (pin "4") (pinfunction "GND_4") (pintype "passive"))
      (node (ref "U7") (pin "7") (pinfunction "EP_7") (pintype "passive"))
      (node (ref "U8") (pin "11") (pinfunction "-V_11") (pintype "power_in"))
      (node (ref "U9") (pin "7") (pinfunction "VSS_7") (pintype "passive"))
      (node (ref "U9") (pin "9") (pinfunction "PAD_9") (pintype "passive"))
      (node (ref "Y1") (pin "2") (pinfunction "2_2") (pintype "passive"))
      (node (ref "Y1") (pin "4") (pinfunction "4_4") (pintype "passive"))
    )
    (net (code "32") (name "Net-(D2-K)") (class "Default")
      (node (ref "D2") (pin "2") (pinfunction "K_2") (pintype "passive"))
      (node (ref "R4") (pin "2") (pinfunction "2_2") (pintype "passive"))
    )
    (net (code "33") (name "Net-(D3-K)") (class "Default")
      (node (ref "D3") (pin "2") (pinfunction "K_2") (pintype "passive"))
      (node (ref "R5") (pin "2") (pinfunction "2_2") (pintype "passive"))
    )
    (net (code "34") (name "Net-(D4-K)") (class "Default")
      (node (ref "D4") (pin "2") (pinfunction "K_2") (pintype "passive"))
      (node (ref "R6") (pin "2") (pinfunction "2_2") (pintype "passive"))
    )
    (net (code "35") (name "Net-(D5-K)") (class "Default")
      (node (ref "C27") (pin "2") (pinfunction "2_2") (pintype "passive"))
      (node (ref "D5") (pin "2") (pinfunction "K_2") (pintype "passive"))
      (node (ref "L2") (pin "1") (pinfunction "1_1") (pintype "passive"))
      (node (ref "U4") (pin "8") (pinfunction "PH_8") (pintype "passive"))
    )
    (net (code "36") (name "Net-(D8-PadA)") (class "Default")
      (node (ref "D8") (pin "A") (pinfunction "A_A") (pintype "passive"))
      (node (ref "Q5") (pin "G") (pinfunction "G_G") (pintype "passive"))
      (node (ref "R18") (pin "2") (pinfunction "2_2") (pintype "passive"))
      (node (ref "R24") (pin "1") (pinfunction "1_1") (pintype "passive"))
    )
    (net (code "37") (name "Net-(D9-K)") (class "Default")
      (node (ref "D9") (pin "2") (pinfunction "K_2") (pintype "passive"))
      (node (ref "U8") (pin "1") (pinfunction "OUT_A_1") (pintype "output"))
    )
    (net (code "38") (name "Net-(L1-Pad1)") (class "Default")
      (node (ref "L1") (pin "1") (pinfunction "1_1") (pintype "passive"))
      (node (ref "L3") (pin "2") (pinfunction "2_2") (pintype "passive"))
    )
    (net (code "39") (name "Net-(Q1-PadG)") (class "Default")
      (node (ref "Q1") (pin "G") (pinfunction "G_G") (pintype "passive"))
      (node (ref "R50") (pin "1") (pinfunction "1_1") (pintype "passive"))
    )
    (net (code "40") (name "Net-(Q2-PadG)") (class "Default")
      (node (ref "Q2") (pin "G") (pinfunction "G_G") (pintype "passive"))
      (node (ref "R48") (pin "1") (pinfunction "1_1") (pintype "passive"))
    )
    (net (code "41") (name "Net-(Q3-PadG)") (class "Default")
      (node (ref "Q3") (pin "G") (pinfunction "G_G") (pintype "passive"))
      (node (ref "R33") (pin "2") (pinfunction "2_2") (pintype "passive"))
    )
    (net (code "42") (name "Net-(Q4-PadG)") (class "Default")
      (node (ref "Q4") (pin "G") (pinfunction "G_G") (pintype "passive"))
      (node (ref "R32") (pin "2") (pinfunction "2_2") (pintype "passive"))
    )
    (net (code "43") (name "Net-(Q7-B)") (class "Default")
      (node (ref "Q7") (pin "2") (pinfunction "B_2") (pintype "passive"))
      (node (ref "R19") (pin "1") (pinfunction "1_1") (pintype "passive"))
      (node (ref "R21") (pin "2") (pinfunction "2_2") (pintype "passive"))
    )
    (net (code "44") (name "Net-(Q7-C)") (class "Default")
      (node (ref "Q7") (pin "1") (pinfunction "C_1") (pintype "passive"))
      (node (ref "R17") (pin "1") (pinfunction "1_1") (pintype "passive"))
      (node (ref "R18") (pin "1") (pinfunction "1_1") (pintype "passive"))
    )
    (net (code "45") (name "Net-(U3-BOOT0)") (class "Default")
      (node (ref "R3") (pin "2") (pinfunction "2_2") (pintype "passive"))
      (node (ref "U3") (pin "44") (pinfunction "BOOT0_44") (pintype "input"))
    )
    (net (code "46") (name "Net-(U4-BOOT)") (class "Default")
      (node (ref "C27") (pin "1") (pinfunction "1_1") (pintype "passive"))
      (node (ref "U4") (pin "1") (pinfunction "BOOT_1") (pintype "passive"))
    )
    (net (code "47") (name "Net-(U4-VSENSE)") (class "Default")
      (node (ref "R10") (pin "1") (pinfunction "1_1") (pintype "passive"))
      (node (ref "R9") (pin "2") (pinfunction "2_2") (pintype "passive"))
      (node (ref "U4") (pin "4") (pinfunction "VSENSE_4") (pintype "passive"))
    )
    (net (code "48") (name "Net-(U5-IN+)") (class "Default")
      (node (ref "C35") (pin "2") (pinfunction "2_2") (pintype "passive"))
      (node (ref "R13") (pin "1") (pinfunction "1_1") (pintype "passive"))
      (node (ref "U5") (pin "2") (pinfunction "IN+_2") (pintype "passive"))
    )
    (net (code "49") (name "Net-(U5-IN-)") (class "Default")
      (node (ref "C35") (pin "1") (pinfunction "1_1") (pintype "passive"))
      (node (ref "R15") (pin "1") (pinfunction "1_1") (pintype "passive"))
      (node (ref "U5") (pin "3") (pinfunction "IN-_3") (pintype "passive"))
    )
    (net (code "50") (name "Net-(U5-OUT)") (class "Default")
      (node (ref "R8") (pin "1") (pinfunction "1_1") (pintype "passive"))
      (node (ref "U5") (pin "8") (pinfunction "OUT_8") (pintype "passive"))
    )
    (net (code "51") (name "Net-(U6-IN+)") (class "Default")
      (node (ref "C34") (pin "2") (pinfunction "2_2") (pintype "passive"))
      (node (ref "R14") (pin "1") (pinfunction "1_1") (pintype "passive"))
      (node (ref "U6") (pin "2") (pinfunction "IN+_2") (pintype "passive"))
    )
    (net (code "52") (name "Net-(U6-IN-)") (class "Default")
      (node (ref "C34") (pin "1") (pinfunction "1_1") (pintype "passive"))
      (node (ref "R12") (pin "1") (pinfunction "1_1") (pintype "passive"))
      (node (ref "U6") (pin "3") (pinfunction "IN-_3") (pintype "passive"))
    )
    (net (code "53") (name "Net-(U6-OUT)") (class "Default")
      (node (ref "R7") (pin "1") (pinfunction "1_1") (pintype "passive"))
      (node (ref "U6") (pin "8") (pinfunction "OUT_8") (pintype "passive"))
    )
    (net (code "54") (name "Net-(U7-GATE)") (class "Default")
      (node (ref "Q6") (pin "G") (pinfunction "G_G") (pintype "passive"))
      (node (ref "U7") (pin "3") (pinfunction "GATE_3") (pintype "passive"))
    )
    (net (code "55") (name "Net-(U7-IN)") (class "Default")
      (node (ref "F1") (pin "2") (pinfunction "2_2") (pintype "passive"))
      (node (ref "Q6") (pin "S") (pinfunction "S_S") (pintype "passive"))
      (node (ref "R23") (pin "2") (pinfunction "2_2") (pintype "passive"))
      (node (ref "U7") (pin "2") (pinfunction "IN_2") (pintype "passive"))
    )
    (net (code "56") (name "Net-(U7-VDD)") (class "Default")
      (node (ref "C39") (pin "2") (pinfunction "2_2") (pintype "passive"))
      (node (ref "R20") (pin "1") (pinfunction "1_1") (pintype "passive"))
      (node (ref "U7") (pin "6") (pinfunction "VDD_6") (pintype "passive"))
    )
    (net (code "57") (name "Net-(U8A--IN_A)") (class "Default")
      (node (ref "C48") (pin "2") (pinfunction "2_2") (pintype "passive"))
      (node (ref "R29") (pin "2") (pinfunction "2_2") (pintype "passive"))
      (node (ref "R30") (pin "1") (pinfunction "1_1") (pintype "passive"))
      (node (ref "U8") (pin "2") (pinfunction "-IN_A_2") (pintype "input"))
    )
    (net (code "58") (name "Net-(U8B-+IN_B)") (class "Default")
      (node (ref "R26") (pin "2") (pinfunction "2_2") (pintype "passive"))
      (node (ref "R27") (pin "2") (pinfunction "2_2") (pintype "passive"))
      (node (ref "U8") (pin "5") (pinfunction "+IN_B_5") (pintype "input"))
    )
    (net (code "59") (name "Net-(U8B--IN_B)") (class "Default")
      (node (ref "R28") (pin "2") (pinfunction "2_2") (pintype "passive"))
      (node (ref "R31") (pin "1") (pinfunction "1_1") (pintype "passive"))
      (node (ref "U8") (pin "6") (pinfunction "-IN_B_6") (pintype "input"))
    )
    (net (code "60") (name "Net-(U8B-OUT_B)") (class "Default")
      (node (ref "R25") (pin "1") (pinfunction "1_1") (pintype "passive"))
      (node (ref "R31") (pin "2") (pinfunction "2_2") (pintype "passive"))
      (node (ref "U8") (pin "7") (pinfunction "OUT_B_7") (pintype "output"))
    )
    (net (code "61") (name "Net-(U8C-+IN_C)") (class "Default")
      (node (ref "C52") (pin "2") (pinfunction "2_2") (pintype "passive"))
      (node (ref "R37") (pin "1") (pinfunction "1_1") (pintype "passive"))
      (node (ref "R38") (pin "2") (pinfunction "2_2") (pintype "passive"))
      (node (ref "U8") (pin "10") (pinfunction "+IN_C_10") (pintype "input"))
    )
    (net (code "62") (name "Net-(U8D-+IN_D)") (class "Default")
      (node (ref "R40") (pin "2") (pinfunction "2_2") (pintype "passive"))
      (node (ref "R41") (pin "2") (pinfunction "2_2") (pintype "passive"))
      (node (ref "U8") (pin "12") (pinfunction "+IN_D_12") (pintype "input"))
    )
    (net (code "63") (name "Net-(U8D--IN_D)") (class "Default")
      (node (ref "R35") (pin "1") (pinfunction "1_1") (pintype "passive"))
      (node (ref "R42") (pin "2") (pinfunction "2_2") (pintype "passive"))
      (node (ref "U8") (pin "13") (pinfunction "-IN_D_13") (pintype "input"))
    )
    (net (code "64") (name "Net-(U8D-OUT_D)") (class "Default")
      (node (ref "R35") (pin "2") (pinfunction "2_2") (pintype "passive"))
      (node (ref "R36") (pin "1") (pinfunction "1_1") (pintype "passive"))
      (node (ref "U8") (pin "14") (pinfunction "OUT_D_14") (pintype "output"))
    )
    (net (code "65") (name "Net-(U9-HB)") (class "Default")
      (node (ref "C28") (pin "2") (pinfunction "2_2") (pintype "passive"))
      (node (ref "U9") (pin "2") (pinfunction "HB_2") (pintype "passive"))
    )
    (net (code "66") (name "Net-(U9-HI)") (class "Default")
      (node (ref "R43") (pin "1") (pinfunction "1_1") (pintype "passive"))
      (node (ref "R44") (pin "1") (pinfunction "1_1") (pintype "passive"))
      (node (ref "U9") (pin "5") (pinfunction "HI_5") (pintype "passive"))
    )
    (net (code "67") (name "Net-(U9-LI)") (class "Default")
      (node (ref "R34") (pin "1") (pinfunction "1_1") (pintype "passive"))
      (node (ref "R39") (pin "2") (pinfunction "2_2") (pintype "passive"))
      (node (ref "U9") (pin "6") (pinfunction "LI_6") (pintype "passive"))
    )
    (net (code "68") (name "Net-(U10-HB)") (class "Default")
      (node (ref "C12") (pin "2") (pinfunction "2_2") (pintype "passive"))
      (node (ref "U10") (pin "2") (pinfunction "HB_2") (pintype "passive"))
    )
    (net (code "69") (name "Net-(U10-HI)") (class "Default")
      (node (ref "R47") (pin "1") (pinfunction "1_1") (pintype "passive"))
      (node (ref "R49") (pin "1") (pinfunction "1_1") (pintype "passive"))
      (node (ref "U10") (pin "5") (pinfunction "HI_5") (pintype "passive"))
    )
    (net (code "70") (name "Net-(U10-LI)") (class "Default")
      (node (ref "R45") (pin "2") (pinfunction "2_2") (pintype "passive"))
      (node (ref "R46") (pin "1") (pinfunction "1_1") (pintype "passive"))
      (node (ref "U10") (pin "6") (pinfunction "LI_6") (pintype "passive"))
    )
    (net (code "71") (name "VBAT") (class "Default")
      (node (ref "D7") (pin "K") (pinfunction "K_K") (pintype "passive"))
      (node (ref "F1") (pin "1") (pinfunction "1_1") (pintype "passive"))
      (node (ref "P5") (pin "1") (pinfunction "1_1") (pintype "passive"))
    )
    (net (code "72") (name "VBAT_N") (class "Default")
      (node (ref "C29") (pin "2") (pinfunction "2_2") (pintype "passive"))
      (node (ref "C31") (pin "2") (pinfunction "2_2") (pintype "passive"))
      (node (ref "C32") (pin "2") (pinfunction "2_2") (pintype "passive"))
      (node (ref "C33") (pin "2") (pinfunction "2_2") (pintype "passive"))
      (node (ref "C36") (pin "2") (pinfunction "2_2") (pintype "passive"))
      (node (ref "D8") (pin "K") (pinfunction "K_K") (pintype "passive"))
      (node (ref "Q4") (pin "D") (pinfunction "D_D") (pintype "passive"))
      (node (ref "Q5") (pin "S") (pinfunction "S_S") (pintype "passive"))
      (node (ref "R15") (pin "2") (pinfunction "2_2") (pintype "passive"))
      (node (ref "R16") (pin "2") (pinfunction "2_2") (pintype "passive"))
      (node (ref "R17") (pin "2") (pinfunction "2_2") (pintype "passive"))
      (node (ref "R24") (pin "2") (pinfunction "2_2") (pintype "passive"))
      (node (ref "R26") (pin "1") (pinfunction "1_1") (pintype "passive"))
      (node (ref "U4") (pin "7") (pinfunction "VIN_7") (pintype "passive"))
    )
    (net (code "73") (name "VBAT_P") (class "Default")
      (node (ref "C40") (pin "2") (pinfunction "2_2") (pintype "passive"))
      (node (ref "C41") (pin "2") (pinfunction "2_2") (pintype "passive"))
      (node (ref "C42") (pin "2") (pinfunction "2_2") (pintype "passive"))
      (node (ref "C43") (pin "2") (pinfunction "2_2") (pintype "passive"))
      (node (ref "Q6") (pin "D") (pinfunction "D_D") (pintype "passive"))
      (node (ref "R13") (pin "2") (pinfunction "2_2") (pintype "passive"))
      (node (ref "R16") (pin "1") (pinfunction "1_1") (pintype "passive"))
      (node (ref "R20") (pin "2") (pinfunction "2_2") (pintype "passive"))
      (node (ref "U7") (pin "1") (pinfunction "OUT_1") (pintype "passive"))
    )
    (net (code "74") (name "VCC_3V3") (class "Default")
      (node (ref "C10") (pin "1") (pinfunction "1_1") (pintype "passive"))
      (node (ref "C11") (pin "2") (pinfunction "2_2") (pintype "passive"))
      (node (ref "C14") (pin "2") (pinfunction "2_2") (pintype "passive"))
      (node (ref "C17") (pin "2") (pinfunction "2_2") (pintype "passive"))
      (node (ref "C21") (pin "2") (pinfunction "2_2") (pintype "passive"))
      (node (ref "C6") (pin "1") (pinfunction "1_1") (pintype "passive"))
      (node (ref "D2") (pin "1") (pinfunction "A_1") (pintype "passive"))
      (node (ref "D3") (pin "1") (pinfunction "A_1") (pintype "passive"))
      (node (ref "D4") (pin "1") (pinfunction "A_1") (pintype "passive"))
      (node (ref "FB1") (pin "1") (pinfunction "1_1") (pintype "passive"))
      (node (ref "P3") (pin "4") (pinfunction "4_4") (pintype "passive"))
      (node (ref "R11") (pin "2") (pinfunction "2_2") (pintype "passive"))
      (node (ref "U1") (pin "3") (pinfunction "VCC_3") (pintype "passive"))
      (node (ref "U2") (pin "2") (pinfunction "OUT_2") (pintype "passive"))
      (node (ref "U3") (pin "1") (pinfunction "VBAT_1") (pintype "power_in"))
      (node (ref "U3") (pin "24") (pinfunction "VDD_1_24") (pintype "power_in"))
      (node (ref "U3") (pin "36") (pinfunction "VDD_2_36") (pintype "power_in"))
      (node (ref "U3") (pin "48") (pinfunction "VDD_3_48") (pintype "power_in"))
    )
    (net (code "75") (name "VCC_10V") (class "Default")
      (node (ref "C15") (pin "1") (pinfunction "1_1") (pintype "passive"))
      (node (ref "C16") (pin "1") (pinfunction "1_1") (pintype "passive"))
      (node (ref "C49") (pin "2") (pinfunction "2_2") (pintype "passive"))
      (node (ref "C53") (pin "2") (pinfunction "2_2") (pintype "passive"))
      (node (ref "L2") (pin "2") (pinfunction "2_2") (pintype "passive"))
      (node (ref "R9") (pin "1") (pinfunction "1_1") (pintype "passive"))
      (node (ref "U10") (pin "1") (pinfunction "VDD_1") (pintype "passive"))
      (node (ref "U2") (pin "3") (pinfunction "IN_3") (pintype "passive"))
      (node (ref "U9") (pin "1") (pinfunction "VDD_1") (pintype "passive"))
    )
    (net (code "76") (name "VOUT") (class "Default")
      (node (ref "C37") (pin "2") (pinfunction "2_2") (pintype "passive"))
      (node (ref "C38") (pin "2") (pinfunction "2_2") (pintype "passive"))
      (node (ref "D6") (pin "K") (pinfunction "K_K") (pintype "passive"))
      (node (ref "P6") (pin "1") (pinfunction "1_1") (pintype "passive"))
      (node (ref "Q5") (pin "D") (pinfunction "D_D") (pintype "passive"))
    )
    (net (code "77") (name "VREF_2V25") (class "Default")
      (node (ref "C24") (pin "1") (pinfunction "1_1") (pintype "passive"))
      (node (ref "C50") (pin "2") (pinfunction "2_2") (pintype "passive"))
      (node (ref "U6") (pin "6") (pinfunction "REF2_6") (pintype "passive"))
      (node (ref "U6") (pin "7") (pinfunction "REF1_7") (pintype "passive"))
      (node (ref "U8") (pin "8") (pinfunction "OUT_C_8") (pintype "output"))
      (node (ref "U8") (pin "9") (pinfunction "-IN_C_9") (pintype "input"))
    )
    (net (code "78") (name "VSCAP_N") (class "Default")
      (node (ref "C1") (pin "2") (pinfunction "2_2") (pintype "passive"))
      (node (ref "C2") (pin "2") (pinfunction "2_2") (pintype "passive"))
      (node (ref "C3") (pin "2") (pinfunction "2_2") (pintype "passive"))
      (node (ref "C4") (pin "2") (pinfunction "2_2") (pintype "passive"))
      (node (ref "D1") (pin "K") (pinfunction "K_K") (pintype "passive"))
      (node (ref "P1") (pin "1") (pinfunction "1_1") (pintype "passive"))
      (node (ref "R1") (pin "1") (pinfunction "1_1") (pintype "passive"))
      (node (ref "R12") (pin "2") (pinfunction "2_2") (pintype "passive"))
      (node (ref "R40") (pin "1") (pinfunction "1_1") (pintype "passive"))
    )
    (net (code "79") (name "VSCAP_P") (class "Default")
      (node (ref "C5") (pin "2") (pinfunction "2_2") (pintype "passive"))
      (node (ref "C7") (pin "2") (pinfunction "2_2") (pintype "passive"))
      (node (ref "C8") (pin "2") (pinfunction "2_2") (pintype "passive"))
      (node (ref "C9") (pin "2") (pinfunction "2_2") (pintype "passive"))
      (node (ref "Q1") (pin "D") (pinfunction "D_D") (pintype "passive"))
      (node (ref "R1") (pin "2") (pinfunction "2_2") (pintype "passive"))
      (node (ref "R14") (pin "2") (pinfunction "2_2") (pintype "passive"))
    )
    (net (code "80") (name "unconnected-(U1-SHDN-Pad5)") (class "Default")
      (node (ref "U1") (pin "5") (pinfunction "SHDN_5") (pintype "passive+no_connect"))
    )
    (net (code "81") (name "unconnected-(U3-PA4-Pad14)") (class "Default")
      (node (ref "U3") (pin "14") (pinfunction "PA4_14") (pintype "bidirectional+no_connect"))
    )
    (net (code "82") (name "unconnected-(U3-PA5-Pad15)") (class "Default")
      (node (ref "U3") (pin "15") (pinfunction "PA5_15") (pintype "bidirectional+no_connect"))
    )
    (net (code "83") (name "unconnected-(U3-PA6-Pad16)") (class "Default")
      (node (ref "U3") (pin "16") (pinfunction "PA6_16") (pintype "bidirectional+no_connect"))
    )
    (net (code "84") (name "unconnected-(U3-PA7-Pad17)") (class "Default")
      (node (ref "U3") (pin "17") (pinfunction "PA7_17") (pintype "bidirectional+no_connect"))
    )
    (net (code "85") (name "unconnected-(U3-PA12-Pad33)") (class "Default")
      (node (ref "U3") (pin "33") (pinfunction "PA12_33") (pintype "bidirectional+no_connect"))
    )
    (net (code "86") (name "unconnected-(U3-PA15{slash}JTDI-Pad38)") (class "Default")
      (node (ref "U3") (pin "38") (pinfunction "PA15/JTDI_38") (pintype "bidirectional+no_connect"))
    )
    (net (code "87") (name "unconnected-(U3-PB0-Pad18)") (class "Default")
      (node (ref "U3") (pin "18") (pinfunction "PB0_18") (pintype "bidirectional+no_connect"))
    )
    (net (code "88") (name "unconnected-(U3-PB1-Pad19)") (class "Default")
      (node (ref "U3") (pin "19") (pinfunction "PB1_19") (pintype "bidirectional+no_connect"))
    )
    (net (code "89") (name "unconnected-(U3-PB2{slash}BOOT1-Pad20)") (class "Default")
      (node (ref "U3") (pin "20") (pinfunction "PB2/BOOT1_20") (pintype "bidirectional+no_connect"))
    )
    (net (code "90") (name "unconnected-(U3-PB5-Pad41)") (class "Default")
      (node (ref "U3") (pin "41") (pinfunction "PB5_41") (pintype "bidirectional+no_connect"))
    )
    (net (code "91") (name "unconnected-(U3-PB10-Pad21)") (class "Default")
      (node (ref "U3") (pin "21") (pinfunction "PB10_21") (pintype "bidirectional+no_connect"))
    )
    (net (code "92") (name "unconnected-(U3-PB11-Pad22)") (class "Default")
      (node (ref "U3") (pin "22") (pinfunction "PB11_22") (pintype "bidirectional+no_connect"))
    )
    (net (code "93") (name "unconnected-(U3-PB12-Pad25)") (class "Default")
      (node (ref "U3") (pin "25") (pinfunction "PB12_25") (pintype "bidirectional+no_connect"))
    )
    (net (code "94") (name "unconnected-(U3-PB13-Pad26)") (class "Default")
      (node (ref "U3") (pin "26") (pinfunction "PB13_26") (pintype "bidirectional+no_connect"))
    )
    (net (code "95") (name "unconnected-(U3-PB14-Pad27)") (class "Default")
      (node (ref "U3") (pin "27") (pinfunction "PB14_27") (pintype "bidirectional+no_connect"))
    )
    (net (code "96") (name "unconnected-(U3-PB15-Pad28)") (class "Default")
      (node (ref "U3") (pin "28") (pinfunction "PB15_28") (pintype "bidirectional+no_connect"))
    )
    (net (code "97") (name "unconnected-(U3-PC13-TAMPER-RTC-Pad2)") (class "Default")
      (node (ref "U3") (pin "2") (pinfunction "PC13-TAMPER-RTC_2") (pintype "bidirectional+no_connect"))
    )
    (net (code "98") (name "unconnected-(U3-PC15-OSC32_OUT-Pad4)") (class "Default")
      (node (ref "U3") (pin "4") (pinfunction "PC15-OSC32_OUT_4") (pintype "bidirectional+no_connect"))
    )
    (net (code "99") (name "unconnected-(U4-ENA-Pad5)") (class "Default")
      (node (ref "U4") (pin "5") (pinfunction "ENA_5") (pintype "passive+no_connect"))
    )
    (net (code "100") (name "unconnected-(U4-NC-Pad2)") (class "Default")
      (node (ref "U4") (pin "2") (pinfunction "NC_2") (pintype "passive+no_connect"))
    )
    (net (code "101") (name "unconnected-(U4-NC-Pad3)") (class "Default")
      (node (ref "U4") (pin "3") (pinfunction "NC_3") (pintype "passive+no_connect"))
    )
    (net (code "102") (name "unconnected-(U5-NC-Pad1)") (class "Default")
      (node (ref "U5") (pin "1") (pinfunction "NC_1") (pintype "passive+no_connect"))
    )
    (net (code "103") (name "unconnected-(U6-NC-Pad1)") (class "Default")
      (node (ref "U6") (pin "1") (pinfunction "NC_1") (pintype "passive+no_connect"))
    )
    (net (code "104") (name "unconnected-(U7-NC-Pad5)") (class "Default")
      (node (ref "U7") (pin "5") (pinfunction "NC_5") (pintype "passive+no_connect"))
    )
    (net (code "105") (name "unconnected-(U8A-+V-Pad4)") (class "Default")
      (node (ref "U8") (pin "4") (pinfunction "+V_4") (pintype "power_in+no_connect"))
    )
    (net (code "106") (name "unconnected-(U8A--V-Pad11)") (class "Default")
      (node (ref "U8") (pin "11") (pinfunction "-V_11") (pintype "power_in+no_connect"))
    )
    (net (code "107") (name "unconnected-(U8B-+V-Pad4)") (class "Default")
      (node (ref "U8") (pin "4") (pinfunction "+V_4") (pintype "power_in+no_connect"))
    )
    (net (code "108") (name "unconnected-(U8B--V-Pad11)") (class "Default")
      (node (ref "U8") (pin "11") (pinfunction "-V_11") (pintype "power_in+no_connect"))
    )
    (net (code "109") (name "unconnected-(U8D-+V-Pad4)") (class "Default")
      (node (ref "U8") (pin "4") (pinfunction "+V_4") (pintype "power_in+no_connect"))
    )
    (net (code "110") (name "unconnected-(U8D--V-Pad11)") (class "Default")
      (node (ref "U8") (pin "11") (pinfunction "-V_11") (pintype "power_in+no_connect"))
    )
  )
)
